# dual-led-wireless-dimmer.net
KiCad netlist of a schematic drawn in EAGLE
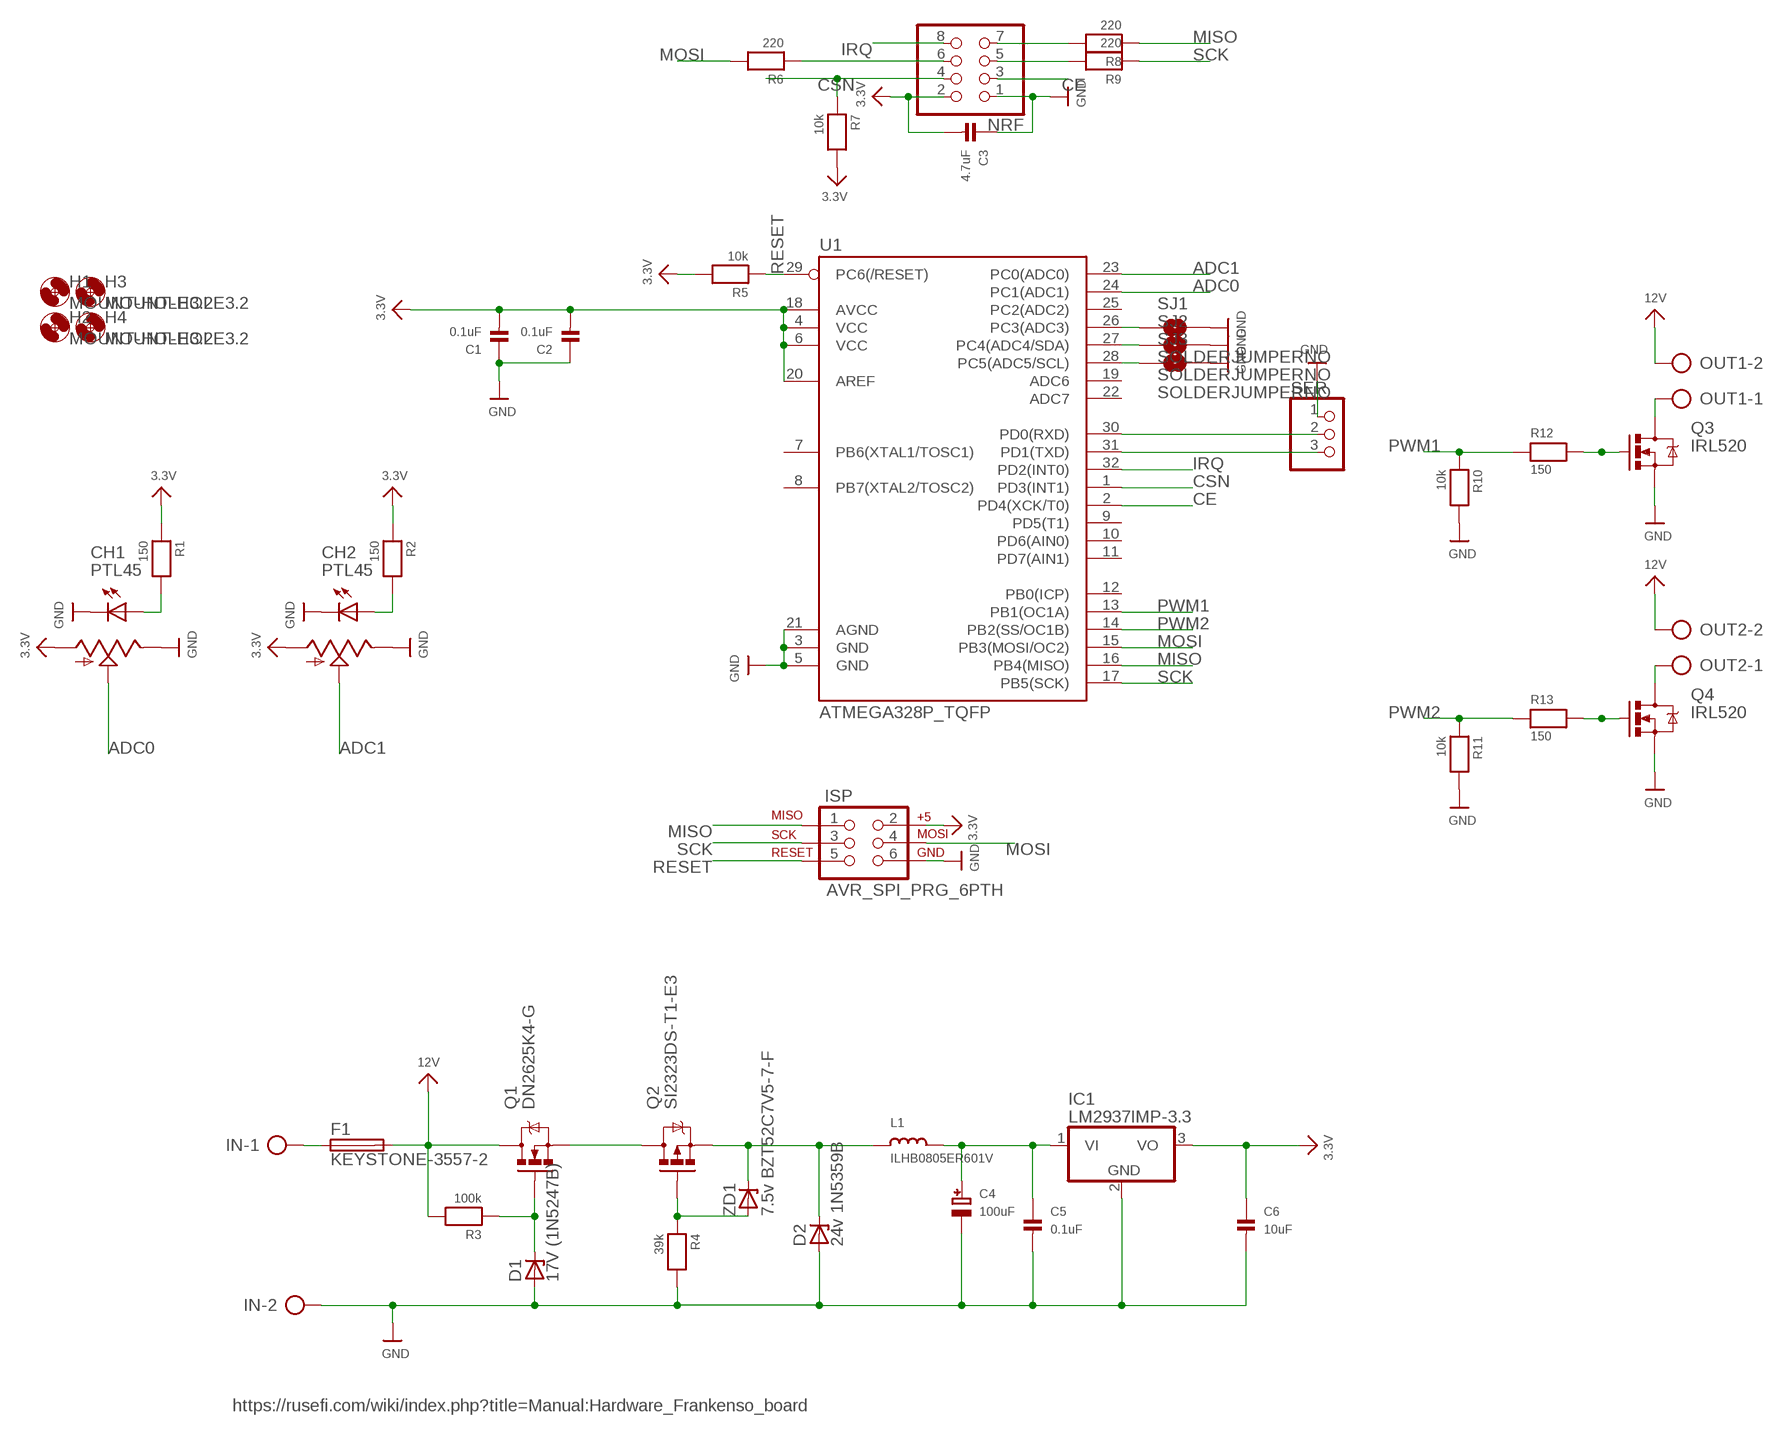
[diagram p0: schematic, sheet 1]

(export (version "E")
  (design (tool "Eeschema 10.0.6"))
  (components
    (comp (ref "C1")
      (value "0.1uF")
      (footprint "eagle-import:0805")
      (libsource (lib "eagle-import") (part "CAP_CERAMIC0805"))
    )
    (comp (ref "C2")
      (value "0.1uF")
      (footprint "eagle-import:0805")
      (libsource (lib "eagle-import") (part "CAP_CERAMIC0805"))
    )
    (comp (ref "C3")
      (value "4.7uF")
      (footprint "eagle-import:0805")
      (libsource (lib "eagle-import") (part "CAP_CERAMIC0805"))
    )
    (comp (ref "C4")
      (value "100uF")
      (footprint "eagle-import:PANASONIC_D")
      (libsource (lib "eagle-import") (part "CAP_ELECTROLYTICPANASONIC_D"))
    )
    (comp (ref "C5")
      (value "0.1uF")
      (footprint "eagle-import:0805")
      (libsource (lib "eagle-import") (part "CAP_CERAMIC0805"))
    )
    (comp (ref "C6")
      (value "10uF")
      (footprint "eagle-import:0805")
      (libsource (lib "eagle-import") (part "CAP_CERAMIC0805"))
    )
    (comp (ref "CH1")
      (value "PTL45")
      (footprint "eagle-import:BOURNS-PTL45")
      (fields (field (name "SPICEPREFIX") "C"))
      (libsource (lib "eagle-import") (part "PTL45"))
    )
    (comp (ref "CH2")
      (value "PTL45")
      (footprint "eagle-import:BOURNS-PTL45")
      (libsource (lib "eagle-import") (part "PTL45"))
    )
    (comp (ref "D1")
      (value "17V (1N5247B)")
      (footprint "eagle-import:ZDIO-5")
      (libsource (lib "eagle-import") (part "ZENER-DIODEZD-5"))
    )
    (comp (ref "D2")
      (value "24v 1N5359B")
      (footprint "eagle-import:DO41Z10")
      (libsource (lib "eagle-import") (part "ZPY"))
    )
    (comp (ref "F1")
      (value "KEYSTONE-3557-2")
      (footprint "eagle-import:KEYSTONE-3557-2")
      (libsource (lib "eagle-import") (part "KEYSTONE-3557-2"))
    )
    (comp (ref "H1")
      (value "MOUNT-HOLE3.2")
      (footprint "eagle-import:3,2")
      (libsource (lib "eagle-import") (part "MOUNT-HOLE3.2"))
    )
    (comp (ref "H2")
      (value "MOUNT-HOLE3.2")
      (footprint "eagle-import:3,2")
      (libsource (lib "eagle-import") (part "MOUNT-HOLE3.2"))
    )
    (comp (ref "H3")
      (value "MOUNT-HOLE3.2")
      (footprint "eagle-import:3,2")
      (libsource (lib "eagle-import") (part "MOUNT-HOLE3.2"))
    )
    (comp (ref "H4")
      (value "MOUNT-HOLE3.2")
      (footprint "eagle-import:3,2")
      (libsource (lib "eagle-import") (part "MOUNT-HOLE3.2"))
    )
    (comp (ref "IC1")
      (value "LM2937IMP-3.3")
      (footprint "eagle-import:TO263-3")
      (libsource (lib "eagle-import") (part "LM2937"))
    )
    (comp (ref "IN")
      (value "AK500/2-H")
      (footprint "eagle-import:AK500_2-H")
      (libsource (lib "eagle-import") (part "AK500/2-H"))
    )
    (comp (ref "ISP")
      (value "AVR_SPI_PRG_6PTH")
      (footprint "eagle-import:2X3")
      (libsource (lib "eagle-import") (part "AVR_SPI_PRG_6PTH"))
    )
    (comp (ref "L1")
      (value "ILHB0805ER601V")
      (footprint "eagle-import:0805")
      (libsource (lib "eagle-import") (part "INDUCTOR0805"))
    )
    (comp (ref "NRF")
      (value "PINHD-2X4")
      (footprint "eagle-import:2X04")
      (libsource (lib "eagle-import") (part "PINHD-2X4"))
    )
    (comp (ref "OUT1")
      (value "AK500/2-H")
      (footprint "eagle-import:AK500_2-H")
      (libsource (lib "eagle-import") (part "AK500/2-H"))
    )
    (comp (ref "OUT2")
      (value "AK500/2-H")
      (footprint "eagle-import:AK500_2-H")
      (libsource (lib "eagle-import") (part "AK500/2-H"))
    )
    (comp (ref "Q1")
      (value "DN2625K4-G")
      (footprint "eagle-import:DPAK")
      (libsource (lib "eagle-import") (part "MOSFET-NCHANNELFDD8780"))
    )
    (comp (ref "Q2")
      (value "SI2323DS-T1-E3")
      (footprint "eagle-import:SOT23-3")
      (libsource (lib "eagle-import") (part "MOSFET-PCHANNEL"))
    )
    (comp (ref "Q3")
      (value "IRL520")
      (footprint "eagle-import:TO220V")
      (libsource (lib "eagle-import") (part "keves-ng_1429743_MOSFET-NCHANNELFQP30N06L"))
    )
    (comp (ref "Q4")
      (value "IRL520")
      (footprint "eagle-import:TO220V")
      (libsource (lib "eagle-import") (part "keves-ng_1429743_MOSFET-NCHANNELFQP30N06L"))
    )
    (comp (ref "R1")
      (value "150")
      (footprint "eagle-import:0805")
      (libsource (lib "eagle-import") (part "RESISTOR0805"))
    )
    (comp (ref "R2")
      (value "150")
      (footprint "eagle-import:0805")
      (libsource (lib "eagle-import") (part "RESISTOR0805"))
    )
    (comp (ref "R3")
      (value "100k")
      (footprint "eagle-import:0805")
      (libsource (lib "eagle-import") (part "RESISTOR0805"))
    )
    (comp (ref "R4")
      (value "39k")
      (footprint "eagle-import:0805")
      (libsource (lib "eagle-import") (part "RESISTOR0805"))
    )
    (comp (ref "R5")
      (value "10k")
      (footprint "eagle-import:0805")
      (libsource (lib "eagle-import") (part "RESISTOR0805"))
    )
    (comp (ref "R6")
      (value "220")
      (footprint "eagle-import:0805")
      (libsource (lib "eagle-import") (part "RESISTOR0805"))
    )
    (comp (ref "R7")
      (value "10k")
      (footprint "eagle-import:0805")
      (libsource (lib "eagle-import") (part "RESISTOR0805"))
    )
    (comp (ref "R8")
      (value "220")
      (footprint "eagle-import:0805")
      (libsource (lib "eagle-import") (part "RESISTOR0805"))
    )
    (comp (ref "R9")
      (value "220")
      (footprint "eagle-import:0805")
      (libsource (lib "eagle-import") (part "RESISTOR0805"))
    )
    (comp (ref "R10")
      (value "10k")
      (footprint "eagle-import:0805")
      (libsource (lib "eagle-import") (part "RESISTOR0805"))
    )
    (comp (ref "R11")
      (value "10k")
      (footprint "eagle-import:0805")
      (libsource (lib "eagle-import") (part "RESISTOR0805"))
    )
    (comp (ref "R12")
      (value "150")
      (footprint "eagle-import:0805")
      (libsource (lib "eagle-import") (part "RESISTOR0805"))
    )
    (comp (ref "R13")
      (value "150")
      (footprint "eagle-import:0805")
      (libsource (lib "eagle-import") (part "RESISTOR0805"))
    )
    (comp (ref "SER")
      (value "PINHD-1X3")
      (footprint "eagle-import:1X03")
      (libsource (lib "eagle-import") (part "PINHD-1X3"))
    )
    (comp (ref "SJ1")
      (value "SOLDERJUMPERNO")
      (footprint "eagle-import:SJ_2S-NO")
      (libsource (lib "eagle-import") (part "SOLDERJUMPERNO"))
    )
    (comp (ref "SJ2")
      (value "SOLDERJUMPERNO")
      (footprint "eagle-import:SJ_2S-NO")
      (libsource (lib "eagle-import") (part "SOLDERJUMPERNO"))
    )
    (comp (ref "SJ3")
      (value "SOLDERJUMPERNO")
      (footprint "eagle-import:SJ_2S-NO")
      (libsource (lib "eagle-import") (part "SOLDERJUMPERNO"))
    )
    (comp (ref "U1")
      (value "ATMEGA328P_TQFP")
      (footprint "eagle-import:TQFP32-08")
      (libsource (lib "eagle-import") (part "ATMEGA328P_TQFP"))
    )
    (comp (ref "ZD1")
      (value "7.5v BZT52C7V5-7-F")
      (footprint "eagle-import:SOD123")
      (libsource (lib "eagle-import") (part "ZD-SOD123"))
    )
  )
  (nets
    (net (code "1") (name "/ADC0") (class "Default")
      (node (ref "CH1") (pin "2") (pinfunction "S_2") (pintype "passive"))
      (node (ref "U1") (pin "24") (pinfunction "PC1(ADC1)_24") (pintype "bidirectional"))
    )
    (net (code "2") (name "/ADC1") (class "Default")
      (node (ref "CH2") (pin "2") (pinfunction "S_2") (pintype "passive"))
      (node (ref "U1") (pin "23") (pinfunction "PC0(ADC0)_23") (pintype "bidirectional"))
    )
    (net (code "3") (name "/CE") (class "Default")
      (node (ref "NRF") (pin "3") (pinfunction "3_3") (pintype "passive"))
      (node (ref "U1") (pin "2") (pinfunction "PD4(XCK/T0)_2") (pintype "bidirectional"))
    )
    (net (code "4") (name "/CSN") (class "Default")
      (node (ref "NRF") (pin "4") (pinfunction "4_4") (pintype "passive"))
      (node (ref "R7") (pin "1") (pinfunction "1_1") (pintype "passive"))
      (node (ref "U1") (pin "1") (pinfunction "PD3(INT1)_1") (pintype "bidirectional"))
    )
    (net (code "5") (name "/IRQ") (class "Default")
      (node (ref "NRF") (pin "8") (pinfunction "8_8") (pintype "passive"))
      (node (ref "U1") (pin "32") (pinfunction "PD2(INT0)_32") (pintype "bidirectional"))
    )
    (net (code "6") (name "/MISO") (class "Default")
      (node (ref "ISP") (pin "1") (pinfunction "1_1") (pintype "passive"))
      (node (ref "R8") (pin "1") (pinfunction "1_1") (pintype "passive"))
      (node (ref "U1") (pin "16") (pinfunction "PB4(MISO)_16") (pintype "bidirectional"))
    )
    (net (code "7") (name "/MOSI") (class "Default")
      (node (ref "ISP") (pin "4") (pinfunction "4_4") (pintype "passive"))
      (node (ref "R6") (pin "2") (pinfunction "2_2") (pintype "passive"))
      (node (ref "U1") (pin "15") (pinfunction "PB3(MOSI/OC2)_15") (pintype "bidirectional"))
    )
    (net (code "8") (name "/PWM1") (class "Default")
      (node (ref "R10") (pin "1") (pinfunction "1_1") (pintype "passive"))
      (node (ref "R12") (pin "1") (pinfunction "1_1") (pintype "passive"))
      (node (ref "U1") (pin "13") (pinfunction "PB1(OC1A)_13") (pintype "bidirectional"))
    )
    (net (code "9") (name "/PWM2") (class "Default")
      (node (ref "R11") (pin "1") (pinfunction "1_1") (pintype "passive"))
      (node (ref "R13") (pin "1") (pinfunction "1_1") (pintype "passive"))
      (node (ref "U1") (pin "14") (pinfunction "PB2(SS/OC1B)_14") (pintype "bidirectional"))
    )
    (net (code "10") (name "/RESET") (class "Default")
      (node (ref "ISP") (pin "5") (pinfunction "5_5") (pintype "passive"))
      (node (ref "R5") (pin "1") (pinfunction "1_1") (pintype "passive"))
      (node (ref "U1") (pin "29") (pinfunction "PC6(/RESET)_29") (pintype "bidirectional"))
    )
    (net (code "11") (name "/SCK") (class "Default")
      (node (ref "ISP") (pin "3") (pinfunction "3_3") (pintype "passive"))
      (node (ref "R9") (pin "1") (pinfunction "1_1") (pintype "passive"))
      (node (ref "U1") (pin "17") (pinfunction "PB5(SCK)_17") (pintype "bidirectional"))
    )
    (net (code "12") (name "3.3V") (class "Default")
      (node (ref "C1") (pin "2") (pinfunction "P$2_2") (pintype "passive"))
      (node (ref "C2") (pin "2") (pinfunction "P$2_2") (pintype "passive"))
      (node (ref "C3") (pin "2") (pinfunction "P$2_2") (pintype "passive"))
      (node (ref "C6") (pin "1") (pinfunction "P$1_1") (pintype "passive"))
      (node (ref "CH1") (pin "1") (pinfunction "A_1") (pintype "passive"))
      (node (ref "CH2") (pin "1") (pinfunction "A_1") (pintype "passive"))
      (node (ref "IC1") (pin "3") (pinfunction "VO_3") (pintype "passive"))
      (node (ref "ISP") (pin "2") (pinfunction "2_2") (pintype "passive"))
      (node (ref "NRF") (pin "2") (pinfunction "2_2") (pintype "passive"))
      (node (ref "R1") (pin "1") (pinfunction "1_1") (pintype "passive"))
      (node (ref "R2") (pin "1") (pinfunction "1_1") (pintype "passive"))
      (node (ref "R5") (pin "2") (pinfunction "2_2") (pintype "passive"))
      (node (ref "R7") (pin "2") (pinfunction "2_2") (pintype "passive"))
      (node (ref "U1") (pin "18") (pinfunction "AVCC_18") (pintype "bidirectional"))
      (node (ref "U1") (pin "20") (pinfunction "AREF_20") (pintype "bidirectional"))
      (node (ref "U1") (pin "4") (pinfunction "VCC_4") (pintype "bidirectional"))
      (node (ref "U1") (pin "6") (pinfunction "VCC_6") (pintype "bidirectional"))
    )
    (net (code "13") (name "12V") (class "Default")
      (node (ref "F1") (pin "R1") (pinfunction "2_R1") (pintype "passive"))
      (node (ref "F1") (pin "R2") (pinfunction "2_R2") (pintype "passive"))
      (node (ref "OUT1") (pin "2") (pinfunction "KL_2") (pintype "passive"))
      (node (ref "OUT2") (pin "2") (pinfunction "KL_2") (pintype "passive"))
      (node (ref "Q1") (pin "4") (pinfunction "D_4") (pintype "passive"))
      (node (ref "R3") (pin "2") (pinfunction "2_2") (pintype "passive"))
    )
    (net (code "14") (name "GND") (class "Default")
      (node (ref "C1") (pin "1") (pinfunction "P$1_1") (pintype "passive"))
      (node (ref "C2") (pin "1") (pinfunction "P$1_1") (pintype "passive"))
      (node (ref "C3") (pin "1") (pinfunction "P$1_1") (pintype "passive"))
      (node (ref "C4") (pin "-") (pinfunction "-_-") (pintype "passive"))
      (node (ref "C5") (pin "2") (pinfunction "P$2_2") (pintype "passive"))
      (node (ref "C6") (pin "2") (pinfunction "P$2_2") (pintype "passive"))
      (node (ref "CH1") (pin "3") (pinfunction "E_3") (pintype "passive"))
      (node (ref "CH1") (pin "E") (pinfunction "LED-_E") (pintype "passive"))
      (node (ref "CH2") (pin "3") (pinfunction "E_3") (pintype "passive"))
      (node (ref "CH2") (pin "E") (pinfunction "LED-_E") (pintype "passive"))
      (node (ref "D1") (pin "A") (pinfunction "A_A") (pintype "passive"))
      (node (ref "D2") (pin "A") (pinfunction "A_A") (pintype "passive"))
      (node (ref "IC1") (pin "2") (pinfunction "GND_2") (pintype "passive"))
      (node (ref "IN") (pin "2") (pinfunction "KL_2") (pintype "passive"))
      (node (ref "ISP") (pin "6") (pinfunction "6_6") (pintype "passive"))
      (node (ref "NRF") (pin "1") (pinfunction "1_1") (pintype "passive"))
      (node (ref "Q3") (pin "3") (pinfunction "S_3") (pintype "passive"))
      (node (ref "Q4") (pin "3") (pinfunction "S_3") (pintype "passive"))
      (node (ref "R10") (pin "2") (pinfunction "2_2") (pintype "passive"))
      (node (ref "R11") (pin "2") (pinfunction "2_2") (pintype "passive"))
      (node (ref "R4") (pin "2") (pinfunction "2_2") (pintype "passive"))
      (node (ref "SER") (pin "1") (pinfunction "1_1") (pintype "passive"))
      (node (ref "SJ1") (pin "2") (pinfunction "2_2") (pintype "passive"))
      (node (ref "SJ2") (pin "2") (pinfunction "2_2") (pintype "passive"))
      (node (ref "SJ3") (pin "2") (pinfunction "2_2") (pintype "passive"))
      (node (ref "U1") (pin "21") (pinfunction "AGND_21") (pintype "bidirectional"))
      (node (ref "U1") (pin "3") (pinfunction "GND_3") (pintype "bidirectional"))
      (node (ref "U1") (pin "5") (pinfunction "GND_5") (pintype "bidirectional"))
    )
    (net (code "15") (name "Net-(C5-P$1)") (class "Default")
      (node (ref "C4") (pin "+") (pinfunction "+_+") (pintype "passive"))
      (node (ref "C5") (pin "1") (pinfunction "P$1_1") (pintype "passive"))
      (node (ref "IC1") (pin "1") (pinfunction "VI_1") (pintype "input"))
      (node (ref "L1") (pin "2") (pinfunction "2_2") (pintype "passive"))
    )
    (net (code "16") (name "Net-(CH1-LED+)") (class "Default")
      (node (ref "CH1") (pin "B") (pinfunction "LED+_B") (pintype "passive"))
      (node (ref "R1") (pin "2") (pinfunction "2_2") (pintype "passive"))
    )
    (net (code "17") (name "Net-(CH2-LED+)") (class "Default")
      (node (ref "CH2") (pin "B") (pinfunction "LED+_B") (pintype "passive"))
      (node (ref "R2") (pin "2") (pinfunction "2_2") (pintype "passive"))
    )
    (net (code "18") (name "Net-(INA-KL)") (class "Default")
      (node (ref "F1") (pin "L1") (pinfunction "1_L1") (pintype "passive"))
      (node (ref "F1") (pin "L2") (pinfunction "1_L2") (pintype "passive"))
      (node (ref "IN") (pin "1") (pinfunction "KL_1") (pintype "passive"))
    )
    (net (code "19") (name "Net-(NRF-Pad5)") (class "Default")
      (node (ref "NRF") (pin "5") (pinfunction "5_5") (pintype "passive"))
      (node (ref "R9") (pin "2") (pinfunction "2_2") (pintype "passive"))
    )
    (net (code "20") (name "Net-(NRF-Pad6)") (class "Default")
      (node (ref "NRF") (pin "6") (pinfunction "6_6") (pintype "passive"))
      (node (ref "R6") (pin "1") (pinfunction "1_1") (pintype "passive"))
    )
    (net (code "21") (name "Net-(NRF-Pad7)") (class "Default")
      (node (ref "NRF") (pin "7") (pinfunction "7_7") (pintype "passive"))
      (node (ref "R8") (pin "2") (pinfunction "2_2") (pintype "passive"))
    )
    (net (code "22") (name "Net-(OUT1A-KL)") (class "Default")
      (node (ref "OUT1") (pin "1") (pinfunction "KL_1") (pintype "passive"))
      (node (ref "Q3") (pin "2") (pinfunction "D_2") (pintype "passive"))
    )
    (net (code "23") (name "Net-(OUT2A-KL)") (class "Default")
      (node (ref "OUT2") (pin "1") (pinfunction "KL_1") (pintype "passive"))
      (node (ref "Q4") (pin "2") (pinfunction "D_2") (pintype "passive"))
    )
    (net (code "24") (name "Net-(Q1-G)") (class "Default")
      (node (ref "D1") (pin "C") (pinfunction "C_C") (pintype "passive"))
      (node (ref "Q1") (pin "1") (pinfunction "G_1") (pintype "passive"))
      (node (ref "R3") (pin "1") (pinfunction "1_1") (pintype "passive"))
    )
    (net (code "25") (name "Net-(Q1-S)") (class "Default")
      (node (ref "Q1") (pin "3") (pinfunction "S_3") (pintype "passive"))
      (node (ref "Q2") (pin "3") (pinfunction "D_3") (pintype "passive"))
    )
    (net (code "26") (name "Net-(Q2-G)") (class "Default")
      (node (ref "Q2") (pin "1") (pinfunction "G_1") (pintype "passive"))
      (node (ref "R4") (pin "1") (pinfunction "1_1") (pintype "passive"))
      (node (ref "ZD1") (pin "A") (pinfunction "A_A") (pintype "passive"))
    )
    (net (code "27") (name "Net-(Q2-S)") (class "Default")
      (node (ref "D2") (pin "C") (pinfunction "C_C") (pintype "passive"))
      (node (ref "L1") (pin "1") (pinfunction "1_1") (pintype "passive"))
      (node (ref "Q2") (pin "2") (pinfunction "S_2") (pintype "passive"))
      (node (ref "ZD1") (pin "C") (pinfunction "C_C") (pintype "passive"))
    )
    (net (code "28") (name "Net-(Q3-G)") (class "Default")
      (node (ref "Q3") (pin "1") (pinfunction "G_1") (pintype "passive"))
      (node (ref "R12") (pin "2") (pinfunction "2_2") (pintype "passive"))
    )
    (net (code "29") (name "Net-(Q4-G)") (class "Default")
      (node (ref "Q4") (pin "1") (pinfunction "G_1") (pintype "passive"))
      (node (ref "R13") (pin "2") (pinfunction "2_2") (pintype "passive"))
    )
    (net (code "30") (name "Net-(U1-PC3(ADC3))") (class "Default")
      (node (ref "SJ1") (pin "1") (pinfunction "1_1") (pintype "passive"))
      (node (ref "U1") (pin "26") (pinfunction "PC3(ADC3)_26") (pintype "bidirectional"))
    )
    (net (code "31") (name "Net-(U1-PC4(ADC4{slash}SDA))") (class "Default")
      (node (ref "SJ2") (pin "1") (pinfunction "1_1") (pintype "passive"))
      (node (ref "U1") (pin "27") (pinfunction "PC4(ADC4/SDA)_27") (pintype "bidirectional"))
    )
    (net (code "32") (name "Net-(U1-PC5(ADC5{slash}SCL))") (class "Default")
      (node (ref "SJ3") (pin "1") (pinfunction "1_1") (pintype "passive"))
      (node (ref "U1") (pin "28") (pinfunction "PC5(ADC5/SCL)_28") (pintype "bidirectional"))
    )
    (net (code "33") (name "Net-(U1-PD0(RXD))") (class "Default")
      (node (ref "SER") (pin "2") (pinfunction "2_2") (pintype "passive"))
      (node (ref "U1") (pin "30") (pinfunction "PD0(RXD)_30") (pintype "bidirectional"))
    )
    (net (code "34") (name "Net-(U1-PD1(TXD))") (class "Default")
      (node (ref "SER") (pin "3") (pinfunction "3_3") (pintype "passive"))
      (node (ref "U1") (pin "31") (pinfunction "PD1(TXD)_31") (pintype "bidirectional"))
    )
    (net (code "35") (name "unconnected-(U1-ADC6-Pad19)") (class "Default")
      (node (ref "U1") (pin "19") (pinfunction "ADC6_19") (pintype "bidirectional"))
    )
    (net (code "36") (name "unconnected-(U1-ADC7-Pad22)") (class "Default")
      (node (ref "U1") (pin "22") (pinfunction "ADC7_22") (pintype "bidirectional"))
    )
    (net (code "37") (name "unconnected-(U1-PB0(ICP)-Pad12)") (class "Default")
      (node (ref "U1") (pin "12") (pinfunction "PB0(ICP)_12") (pintype "bidirectional"))
    )
    (net (code "38") (name "unconnected-(U1-PB6(XTAL1{slash}TOSC1)-Pad7)") (class "Default")
      (node (ref "U1") (pin "7") (pinfunction "PB6(XTAL1/TOSC1)_7") (pintype "bidirectional"))
    )
    (net (code "39") (name "unconnected-(U1-PB7(XTAL2{slash}TOSC2)-Pad8)") (class "Default")
      (node (ref "U1") (pin "8") (pinfunction "PB7(XTAL2/TOSC2)_8") (pintype "bidirectional"))
    )
    (net (code "40") (name "unconnected-(U1-PC2(ADC2)-Pad25)") (class "Default")
      (node (ref "U1") (pin "25") (pinfunction "PC2(ADC2)_25") (pintype "bidirectional"))
    )
    (net (code "41") (name "unconnected-(U1-PD5(T1)-Pad9)") (class "Default")
      (node (ref "U1") (pin "9") (pinfunction "PD5(T1)_9") (pintype "bidirectional"))
    )
    (net (code "42") (name "unconnected-(U1-PD6(AIN0)-Pad10)") (class "Default")
      (node (ref "U1") (pin "10") (pinfunction "PD6(AIN0)_10") (pintype "bidirectional"))
    )
    (net (code "43") (name "unconnected-(U1-PD7(AIN1)-Pad11)") (class "Default")
      (node (ref "U1") (pin "11") (pinfunction "PD7(AIN1)_11") (pintype "bidirectional"))
    )
  )
)
